# Light_Sensor.net
KiCad netlist of a schematic drawn in EAGLE
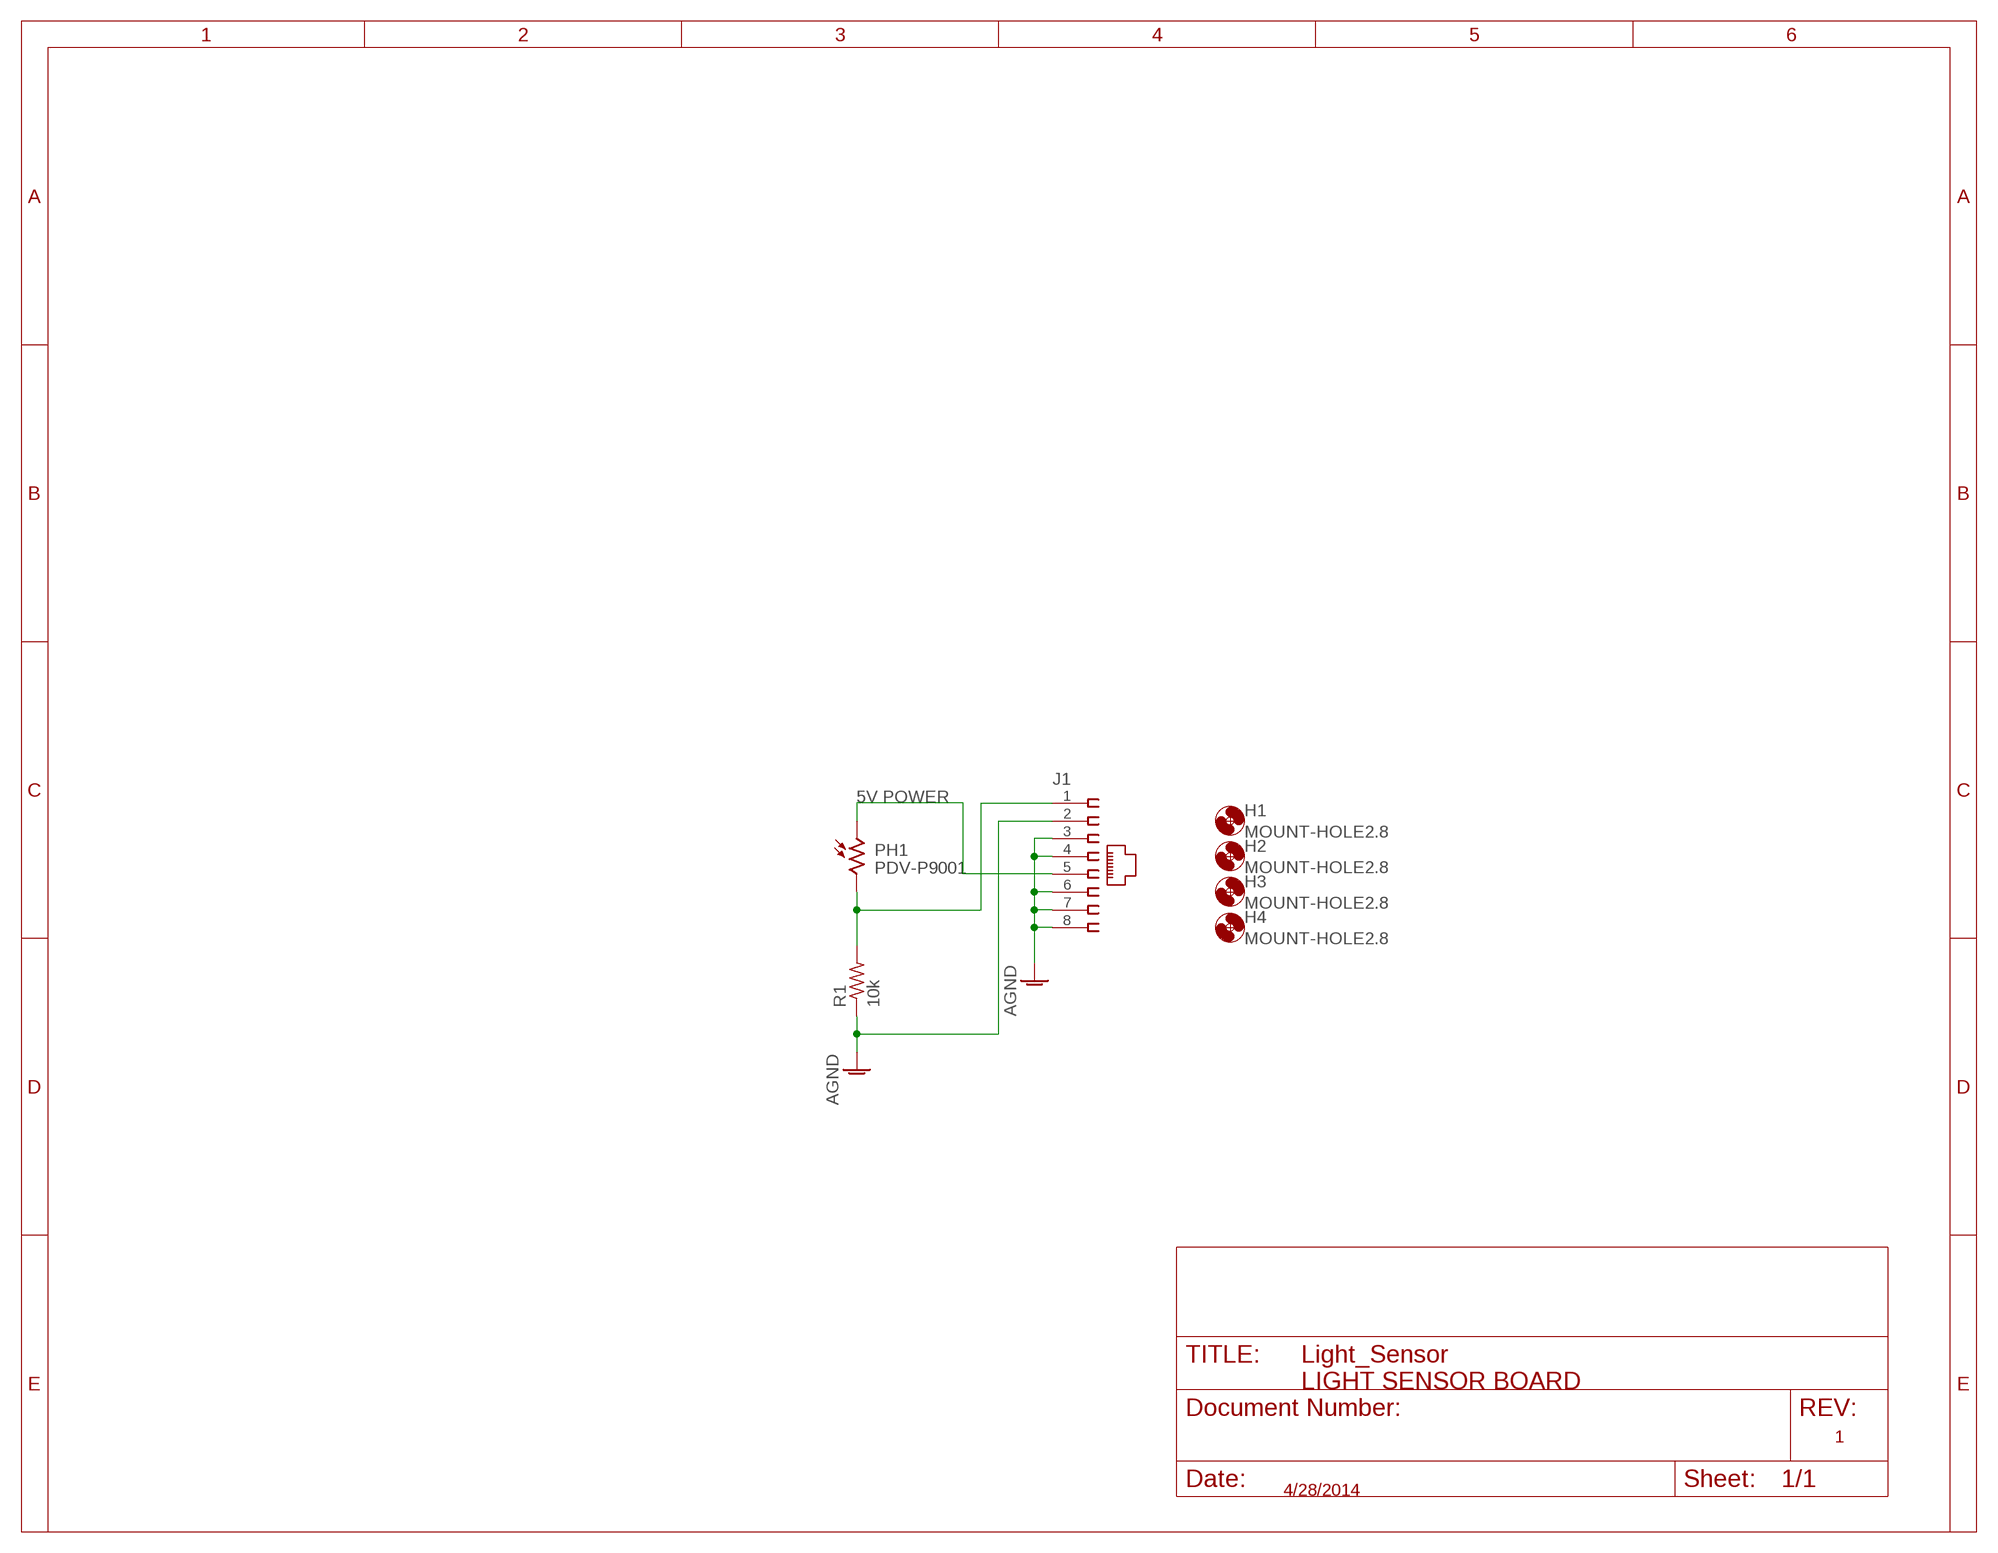
[diagram p0: schematic, sheet 1]

(export (version "E")
  (design (tool "Eeschema 10.0.6"))
  (components
    (comp (ref "H1")
      (value "MOUNT-HOLE2.8")
      (footprint "eagle-import:2,8")
      (libsource (lib "eagle-import") (part "MOUNT-HOLE2.8"))
    )
    (comp (ref "H2")
      (value "MOUNT-HOLE2.8")
      (footprint "eagle-import:2,8")
      (libsource (lib "eagle-import") (part "MOUNT-HOLE2.8"))
    )
    (comp (ref "H3")
      (value "MOUNT-HOLE2.8")
      (footprint "eagle-import:2,8")
      (libsource (lib "eagle-import") (part "MOUNT-HOLE2.8"))
    )
    (comp (ref "H4")
      (value "MOUNT-HOLE2.8")
      (footprint "eagle-import:2,8")
      (libsource (lib "eagle-import") (part "MOUNT-HOLE2.8"))
    )
    (comp (ref "J1")
      (value "555167-1")
      (footprint "eagle-import:555167-1")
      (libsource (lib "eagle-import") (part "555167-1"))
    )
    (comp (ref "PH1")
      (value "VT83N2")
      (footprint "eagle-import:VT800")
      (libsource (lib "eagle-import") (part "VT83N2"))
    )
    (comp (ref "R1")
      (value "10k")
      (footprint "eagle-import:R1206")
      (libsource (lib "eagle-import") (part "R-US_R1206"))
    )
  )
  (nets
    (net (code "1") (name "AGND") (class "Default")
      (node (ref "J1") (pin "2") (pinfunction "2_2") (pintype "passive"))
      (node (ref "J1") (pin "3") (pinfunction "3_3") (pintype "passive"))
      (node (ref "J1") (pin "4") (pinfunction "4_4") (pintype "passive"))
      (node (ref "J1") (pin "6") (pinfunction "6_6") (pintype "passive"))
      (node (ref "J1") (pin "7") (pinfunction "7_7") (pintype "passive"))
      (node (ref "J1") (pin "8") (pinfunction "8_8") (pintype "passive"))
      (node (ref "R1") (pin "1") (pinfunction "1_1") (pintype "passive"))
    )
    (net (code "2") (name "Net-(J1-Pad1)") (class "Default")
      (node (ref "J1") (pin "1") (pinfunction "1_1") (pintype "passive"))
      (node (ref "PH1") (pin "2") (pinfunction "2_2") (pintype "passive"))
      (node (ref "R1") (pin "2") (pinfunction "2_2") (pintype "passive"))
    )
    (net (code "3") (name "Net-(J1-Pad5)") (class "Default")
      (node (ref "J1") (pin "5") (pinfunction "5_5") (pintype "passive"))
      (node (ref "PH1") (pin "1") (pinfunction "1_1") (pintype "passive"))
    )
  )
)
